# passive_balancing.net
KiCad netlist of a schematic drawn in Altium Designer
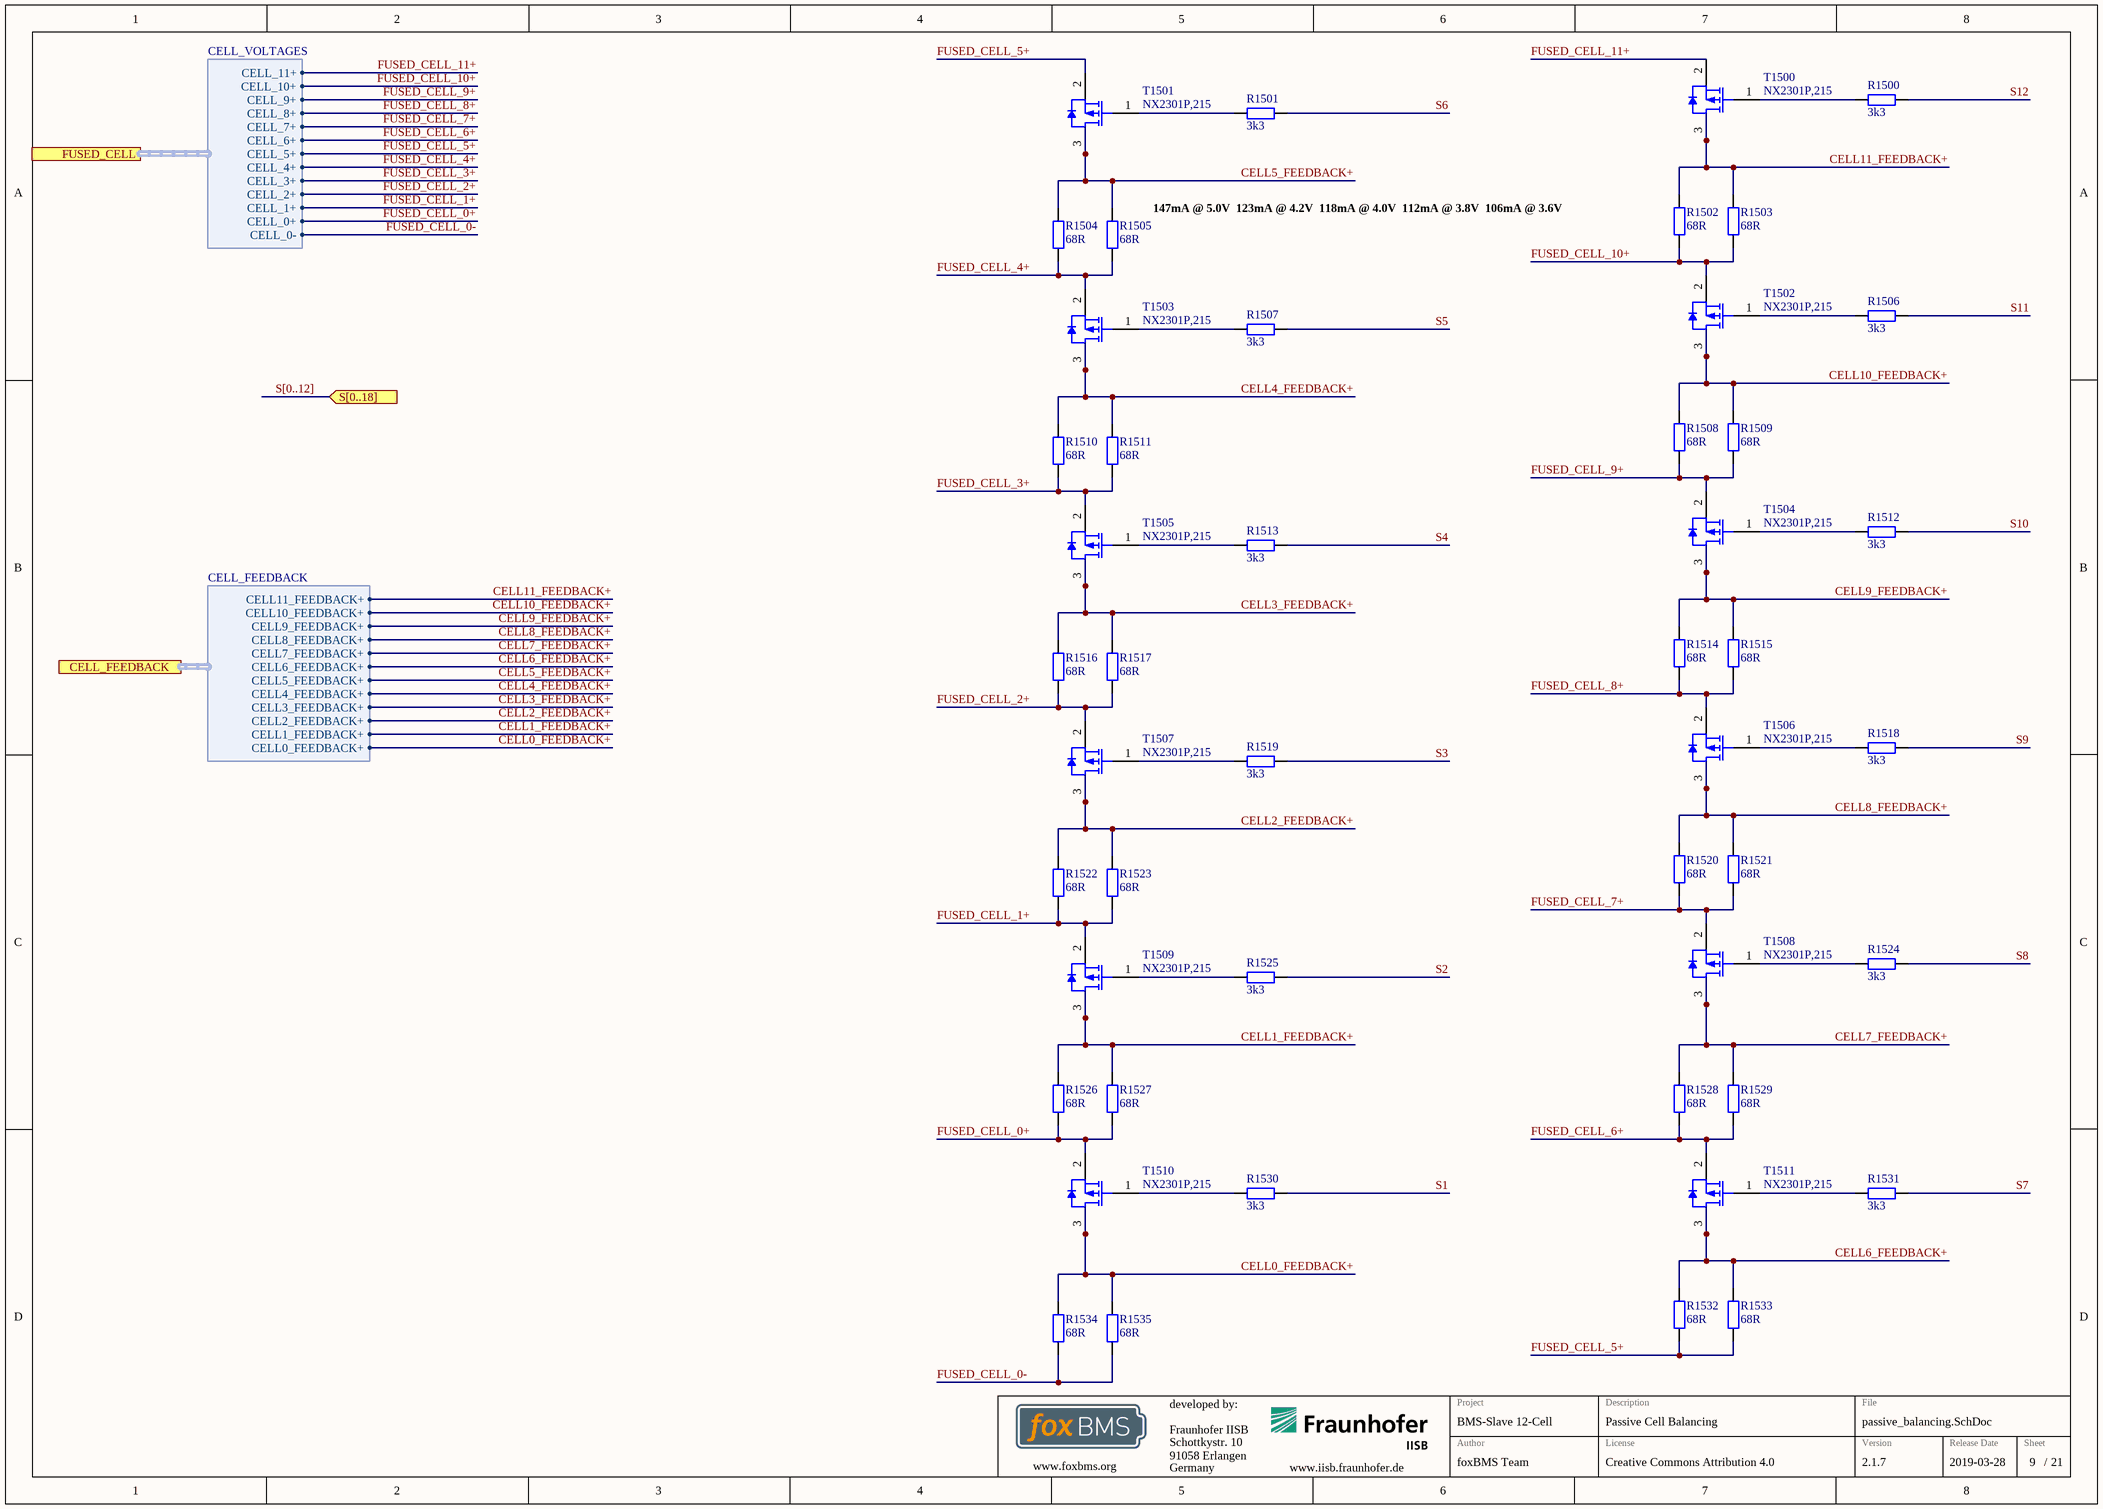
[diagram p0: passive_balancing.SchDoc]

(export (version "E")
  (design (tool "Eeschema 10.0.6"))
  (components
    (comp (ref "R1500")
      (value "3k3")
      (footprint "RESC1608X05N")
      (description "SMD Resistor 3k3 0603")
      (fields (field (name "PART NUMBER") "gen_R_3k3_0603") (field (name "TOLERANCE") "1%"))
      (libsource (lib "OE750") (part "R"))
    )
    (comp (ref "R1501")
      (value "3k3")
      (footprint "RESC1608X05N")
      (description "SMD Resistor 3k3 0603")
      (fields (field (name "PART NUMBER") "gen_R_3k3_0603") (field (name "TOLERANCE") "1%"))
      (libsource (lib "OE750") (part "R"))
    )
    (comp (ref "R1502")
      (value "68R")
      (footprint "RESC5025X07N")
      (description "SMD Resistor 68R 2010")
      (fields (field (name "PART NUMBER") "gen_R_68R_2010") (field (name "TOLERANCE") "1%"))
      (libsource (lib "OE750") (part "R"))
    )
    (comp (ref "R1503")
      (value "68R")
      (footprint "RESC5025X07N")
      (description "SMD Resistor 68R 2010")
      (fields (field (name "PART NUMBER") "gen_R_68R_2010") (field (name "TOLERANCE") "1%"))
      (libsource (lib "OE750") (part "R"))
    )
    (comp (ref "R1504")
      (value "68R")
      (footprint "RESC5025X07N")
      (description "SMD Resistor 68R 2010")
      (fields (field (name "PART NUMBER") "gen_R_68R_2010") (field (name "TOLERANCE") "1%"))
      (libsource (lib "OE750") (part "R"))
    )
    (comp (ref "R1505")
      (value "68R")
      (footprint "RESC5025X07N")
      (description "SMD Resistor 68R 2010")
      (fields (field (name "PART NUMBER") "gen_R_68R_2010") (field (name "TOLERANCE") "1%"))
      (libsource (lib "OE750") (part "R"))
    )
    (comp (ref "R1506")
      (value "3k3")
      (footprint "RESC1608X05N")
      (description "SMD Resistor 3k3 0603")
      (fields (field (name "PART NUMBER") "gen_R_3k3_0603") (field (name "TOLERANCE") "1%"))
      (libsource (lib "OE750") (part "R"))
    )
    (comp (ref "R1507")
      (value "3k3")
      (footprint "RESC1608X05N")
      (description "SMD Resistor 3k3 0603")
      (fields (field (name "PART NUMBER") "gen_R_3k3_0603") (field (name "TOLERANCE") "1%"))
      (libsource (lib "OE750") (part "R"))
    )
    (comp (ref "R1508")
      (value "68R")
      (footprint "RESC5025X07N")
      (description "SMD Resistor 68R 2010")
      (fields (field (name "PART NUMBER") "gen_R_68R_2010") (field (name "TOLERANCE") "1%"))
      (libsource (lib "OE750") (part "R"))
    )
    (comp (ref "R1509")
      (value "68R")
      (footprint "RESC5025X07N")
      (description "SMD Resistor 68R 2010")
      (fields (field (name "PART NUMBER") "gen_R_68R_2010") (field (name "TOLERANCE") "1%"))
      (libsource (lib "OE750") (part "R"))
    )
    (comp (ref "R1510")
      (value "68R")
      (footprint "RESC5025X07N")
      (description "SMD Resistor 68R 2010")
      (fields (field (name "PART NUMBER") "gen_R_68R_2010") (field (name "TOLERANCE") "1%"))
      (libsource (lib "OE750") (part "R"))
    )
    (comp (ref "R1511")
      (value "68R")
      (footprint "RESC5025X07N")
      (description "SMD Resistor 68R 2010")
      (fields (field (name "PART NUMBER") "gen_R_68R_2010") (field (name "TOLERANCE") "1%"))
      (libsource (lib "OE750") (part "R"))
    )
    (comp (ref "R1512")
      (value "3k3")
      (footprint "RESC1608X05N")
      (description "SMD Resistor 3k3 0603")
      (fields (field (name "PART NUMBER") "gen_R_3k3_0603") (field (name "TOLERANCE") "1%"))
      (libsource (lib "OE750") (part "R"))
    )
    (comp (ref "R1513")
      (value "3k3")
      (footprint "RESC1608X05N")
      (description "SMD Resistor 3k3 0603")
      (fields (field (name "PART NUMBER") "gen_R_3k3_0603") (field (name "TOLERANCE") "1%"))
      (libsource (lib "OE750") (part "R"))
    )
    (comp (ref "R1514")
      (value "68R")
      (footprint "RESC5025X07N")
      (description "SMD Resistor 68R 2010")
      (fields (field (name "PART NUMBER") "gen_R_68R_2010") (field (name "TOLERANCE") "1%"))
      (libsource (lib "OE750") (part "R"))
    )
    (comp (ref "R1515")
      (value "68R")
      (footprint "RESC5025X07N")
      (description "SMD Resistor 68R 2010")
      (fields (field (name "PART NUMBER") "gen_R_68R_2010") (field (name "TOLERANCE") "1%"))
      (libsource (lib "OE750") (part "R"))
    )
    (comp (ref "R1516")
      (value "68R")
      (footprint "RESC5025X07N")
      (description "SMD Resistor 68R 2010")
      (fields (field (name "PART NUMBER") "gen_R_68R_2010") (field (name "TOLERANCE") "1%"))
      (libsource (lib "OE750") (part "R"))
    )
    (comp (ref "R1517")
      (value "68R")
      (footprint "RESC5025X07N")
      (description "SMD Resistor 68R 2010")
      (fields (field (name "PART NUMBER") "gen_R_68R_2010") (field (name "TOLERANCE") "1%"))
      (libsource (lib "OE750") (part "R"))
    )
    (comp (ref "R1518")
      (value "3k3")
      (footprint "RESC1608X05N")
      (description "SMD Resistor 3k3 0603")
      (fields (field (name "PART NUMBER") "gen_R_3k3_0603") (field (name "TOLERANCE") "1%"))
      (libsource (lib "OE750") (part "R"))
    )
    (comp (ref "R1519")
      (value "3k3")
      (footprint "RESC1608X05N")
      (description "SMD Resistor 3k3 0603")
      (fields (field (name "PART NUMBER") "gen_R_3k3_0603") (field (name "TOLERANCE") "1%"))
      (libsource (lib "OE750") (part "R"))
    )
    (comp (ref "R1520")
      (value "68R")
      (footprint "RESC5025X07N")
      (description "SMD Resistor 68R 2010")
      (fields (field (name "PART NUMBER") "gen_R_68R_2010") (field (name "TOLERANCE") "1%"))
      (libsource (lib "OE750") (part "R"))
    )
    (comp (ref "R1521")
      (value "68R")
      (footprint "RESC5025X07N")
      (description "SMD Resistor 68R 2010")
      (fields (field (name "PART NUMBER") "gen_R_68R_2010") (field (name "TOLERANCE") "1%"))
      (libsource (lib "OE750") (part "R"))
    )
    (comp (ref "R1522")
      (value "68R")
      (footprint "RESC5025X07N")
      (description "SMD Resistor 68R 2010")
      (fields (field (name "PART NUMBER") "gen_R_68R_2010") (field (name "TOLERANCE") "1%"))
      (libsource (lib "OE750") (part "R"))
    )
    (comp (ref "R1523")
      (value "68R")
      (footprint "RESC5025X07N")
      (description "SMD Resistor 68R 2010")
      (fields (field (name "PART NUMBER") "gen_R_68R_2010") (field (name "TOLERANCE") "1%"))
      (libsource (lib "OE750") (part "R"))
    )
    (comp (ref "R1524")
      (value "3k3")
      (footprint "RESC1608X05N")
      (description "SMD Resistor 3k3 0603")
      (fields (field (name "PART NUMBER") "gen_R_3k3_0603") (field (name "TOLERANCE") "1%"))
      (libsource (lib "OE750") (part "R"))
    )
    (comp (ref "R1525")
      (value "3k3")
      (footprint "RESC1608X05N")
      (description "SMD Resistor 3k3 0603")
      (fields (field (name "PART NUMBER") "gen_R_3k3_0603") (field (name "TOLERANCE") "1%"))
      (libsource (lib "OE750") (part "R"))
    )
    (comp (ref "R1526")
      (value "68R")
      (footprint "RESC5025X07N")
      (description "SMD Resistor 68R 2010")
      (fields (field (name "PART NUMBER") "gen_R_68R_2010") (field (name "TOLERANCE") "1%"))
      (libsource (lib "OE750") (part "R"))
    )
    (comp (ref "R1527")
      (value "68R")
      (footprint "RESC5025X07N")
      (description "SMD Resistor 68R 2010")
      (fields (field (name "PART NUMBER") "gen_R_68R_2010") (field (name "TOLERANCE") "1%"))
      (libsource (lib "OE750") (part "R"))
    )
    (comp (ref "R1528")
      (value "68R")
      (footprint "RESC5025X07N")
      (description "SMD Resistor 68R 2010")
      (fields (field (name "PART NUMBER") "gen_R_68R_2010") (field (name "TOLERANCE") "1%"))
      (libsource (lib "OE750") (part "R"))
    )
    (comp (ref "R1529")
      (value "68R")
      (footprint "RESC5025X07N")
      (description "SMD Resistor 68R 2010")
      (fields (field (name "PART NUMBER") "gen_R_68R_2010") (field (name "TOLERANCE") "1%"))
      (libsource (lib "OE750") (part "R"))
    )
    (comp (ref "R1530")
      (value "3k3")
      (footprint "RESC1608X05N")
      (description "SMD Resistor 3k3 0603")
      (fields (field (name "PART NUMBER") "gen_R_3k3_0603") (field (name "TOLERANCE") "1%"))
      (libsource (lib "OE750") (part "R"))
    )
    (comp (ref "R1531")
      (value "3k3")
      (footprint "RESC1608X05N")
      (description "SMD Resistor 3k3 0603")
      (fields (field (name "PART NUMBER") "gen_R_3k3_0603") (field (name "TOLERANCE") "1%"))
      (libsource (lib "OE750") (part "R"))
    )
    (comp (ref "R1532")
      (value "68R")
      (footprint "RESC5025X07N")
      (description "SMD Resistor 68R 2010")
      (fields (field (name "PART NUMBER") "gen_R_68R_2010") (field (name "TOLERANCE") "1%"))
      (libsource (lib "OE750") (part "R"))
    )
    (comp (ref "R1533")
      (value "68R")
      (footprint "RESC5025X07N")
      (description "SMD Resistor 68R 2010")
      (fields (field (name "PART NUMBER") "gen_R_68R_2010") (field (name "TOLERANCE") "1%"))
      (libsource (lib "OE750") (part "R"))
    )
    (comp (ref "R1534")
      (value "68R")
      (footprint "RESC5025X07N")
      (description "SMD Resistor 68R 2010")
      (fields (field (name "PART NUMBER") "gen_R_68R_2010") (field (name "TOLERANCE") "1%"))
      (libsource (lib "OE750") (part "R"))
    )
    (comp (ref "R1535")
      (value "68R")
      (footprint "RESC5025X07N")
      (description "SMD Resistor 68R 2010")
      (fields (field (name "PART NUMBER") "gen_R_68R_2010") (field (name "TOLERANCE") "1%"))
      (libsource (lib "OE750") (part "R"))
    )
    (comp (ref "T1500")
      (value "NX2301P,215")
      (footprint "NXP-SOT23_N")
      (description "P-Channel Trench MOSFET, -20 V, -2 A, -55 to 150 degC, 3-Pin SOT23, Tape and Reel")
      (fields (field (name "MANUFACTURER") "NXP Semiconductors"))
      (libsource (lib "Altium Content Vault") (part "NXP-PMOS-GSD-3"))
    )
    (comp (ref "T1501")
      (value "NX2301P,215")
      (footprint "NXP-SOT23_N")
      (description "P-Channel Trench MOSFET, -20 V, -2 A, -55 to 150 degC, 3-Pin SOT23, Tape and Reel")
      (fields (field (name "MANUFACTURER") "NXP Semiconductors"))
      (libsource (lib "Altium Content Vault") (part "NXP-PMOS-GSD-3"))
    )
    (comp (ref "T1502")
      (value "NX2301P,215")
      (footprint "NXP-SOT23_N")
      (description "P-Channel Trench MOSFET, -20 V, -2 A, -55 to 150 degC, 3-Pin SOT23, Tape and Reel")
      (fields (field (name "MANUFACTURER") "NXP Semiconductors"))
      (libsource (lib "Altium Content Vault") (part "NXP-PMOS-GSD-3"))
    )
    (comp (ref "T1503")
      (value "NX2301P,215")
      (footprint "NXP-SOT23_N")
      (description "P-Channel Trench MOSFET, -20 V, -2 A, -55 to 150 degC, 3-Pin SOT23, Tape and Reel")
      (fields (field (name "MANUFACTURER") "NXP Semiconductors"))
      (libsource (lib "Altium Content Vault") (part "NXP-PMOS-GSD-3"))
    )
    (comp (ref "T1504")
      (value "NX2301P,215")
      (footprint "NXP-SOT23_N")
      (description "P-Channel Trench MOSFET, -20 V, -2 A, -55 to 150 degC, 3-Pin SOT23, Tape and Reel")
      (fields (field (name "MANUFACTURER") "NXP Semiconductors"))
      (libsource (lib "Altium Content Vault") (part "NXP-PMOS-GSD-3"))
    )
    (comp (ref "T1505")
      (value "NX2301P,215")
      (footprint "NXP-SOT23_N")
      (description "P-Channel Trench MOSFET, -20 V, -2 A, -55 to 150 degC, 3-Pin SOT23, Tape and Reel")
      (fields (field (name "MANUFACTURER") "NXP Semiconductors"))
      (libsource (lib "Altium Content Vault") (part "NXP-PMOS-GSD-3"))
    )
    (comp (ref "T1506")
      (value "NX2301P,215")
      (footprint "NXP-SOT23_N")
      (description "P-Channel Trench MOSFET, -20 V, -2 A, -55 to 150 degC, 3-Pin SOT23, Tape and Reel")
      (fields (field (name "MANUFACTURER") "NXP Semiconductors"))
      (libsource (lib "Altium Content Vault") (part "NXP-PMOS-GSD-3"))
    )
    (comp (ref "T1507")
      (value "NX2301P,215")
      (footprint "NXP-SOT23_N")
      (description "P-Channel Trench MOSFET, -20 V, -2 A, -55 to 150 degC, 3-Pin SOT23, Tape and Reel")
      (fields (field (name "MANUFACTURER") "NXP Semiconductors"))
      (libsource (lib "Altium Content Vault") (part "NXP-PMOS-GSD-3"))
    )
    (comp (ref "T1508")
      (value "NX2301P,215")
      (footprint "NXP-SOT23_N")
      (description "P-Channel Trench MOSFET, -20 V, -2 A, -55 to 150 degC, 3-Pin SOT23, Tape and Reel")
      (fields (field (name "MANUFACTURER") "NXP Semiconductors"))
      (libsource (lib "Altium Content Vault") (part "NXP-PMOS-GSD-3"))
    )
    (comp (ref "T1509")
      (value "NX2301P,215")
      (footprint "NXP-SOT23_N")
      (description "P-Channel Trench MOSFET, -20 V, -2 A, -55 to 150 degC, 3-Pin SOT23, Tape and Reel")
      (fields (field (name "MANUFACTURER") "NXP Semiconductors"))
      (libsource (lib "Altium Content Vault") (part "NXP-PMOS-GSD-3"))
    )
    (comp (ref "T1510")
      (value "NX2301P,215")
      (footprint "NXP-SOT23_N")
      (description "P-Channel Trench MOSFET, -20 V, -2 A, -55 to 150 degC, 3-Pin SOT23, Tape and Reel")
      (fields (field (name "MANUFACTURER") "NXP Semiconductors"))
      (libsource (lib "Altium Content Vault") (part "NXP-PMOS-GSD-3"))
    )
    (comp (ref "T1511")
      (value "NX2301P,215")
      (footprint "NXP-SOT23_N")
      (description "P-Channel Trench MOSFET, -20 V, -2 A, -55 to 150 degC, 3-Pin SOT23, Tape and Reel")
      (fields (field (name "MANUFACTURER") "NXP Semiconductors"))
      (libsource (lib "Altium Content Vault") (part "NXP-PMOS-GSD-3"))
    )
  )
  (nets
    (net (code "4") (name "/CELL0_FEEDBACK+") (class "Default")
      (node (ref "R1534") (pin "2") (pinfunction "2_2") (pintype "passive"))
      (node (ref "R1535") (pin "2") (pinfunction "2_2") (pintype "passive"))
      (node (ref "T1510") (pin "3") (pinfunction "D_3") (pintype "passive"))
    )
    (net (code "5") (name "/CELL1_FEEDBACK+") (class "Default")
      (node (ref "R1526") (pin "2") (pinfunction "2_2") (pintype "passive"))
      (node (ref "R1527") (pin "2") (pinfunction "2_2") (pintype "passive"))
      (node (ref "T1509") (pin "3") (pinfunction "D_3") (pintype "passive"))
    )
    (net (code "6") (name "/CELL2_FEEDBACK+") (class "Default")
      (node (ref "R1522") (pin "2") (pinfunction "2_2") (pintype "passive"))
      (node (ref "R1523") (pin "2") (pinfunction "2_2") (pintype "passive"))
      (node (ref "T1507") (pin "3") (pinfunction "D_3") (pintype "passive"))
    )
    (net (code "7") (name "/CELL3_FEEDBACK+") (class "Default")
      (node (ref "R1516") (pin "2") (pinfunction "2_2") (pintype "passive"))
      (node (ref "R1517") (pin "2") (pinfunction "2_2") (pintype "passive"))
      (node (ref "T1505") (pin "3") (pinfunction "D_3") (pintype "passive"))
    )
    (net (code "8") (name "/CELL4_FEEDBACK+") (class "Default")
      (node (ref "R1510") (pin "2") (pinfunction "2_2") (pintype "passive"))
      (node (ref "R1511") (pin "2") (pinfunction "2_2") (pintype "passive"))
      (node (ref "T1503") (pin "3") (pinfunction "D_3") (pintype "passive"))
    )
    (net (code "9") (name "/CELL5_FEEDBACK+") (class "Default")
      (node (ref "R1504") (pin "2") (pinfunction "2_2") (pintype "passive"))
      (node (ref "R1505") (pin "2") (pinfunction "2_2") (pintype "passive"))
      (node (ref "T1501") (pin "3") (pinfunction "D_3") (pintype "passive"))
    )
    (net (code "10") (name "/CELL6_FEEDBACK+") (class "Default")
      (node (ref "R1532") (pin "2") (pinfunction "2_2") (pintype "passive"))
      (node (ref "R1533") (pin "2") (pinfunction "2_2") (pintype "passive"))
      (node (ref "T1511") (pin "3") (pinfunction "D_3") (pintype "passive"))
    )
    (net (code "11") (name "/CELL7_FEEDBACK+") (class "Default")
      (node (ref "R1528") (pin "2") (pinfunction "2_2") (pintype "passive"))
      (node (ref "R1529") (pin "2") (pinfunction "2_2") (pintype "passive"))
      (node (ref "T1508") (pin "3") (pinfunction "D_3") (pintype "passive"))
    )
    (net (code "12") (name "/CELL8_FEEDBACK+") (class "Default")
      (node (ref "R1520") (pin "2") (pinfunction "2_2") (pintype "passive"))
      (node (ref "R1521") (pin "2") (pinfunction "2_2") (pintype "passive"))
      (node (ref "T1506") (pin "3") (pinfunction "D_3") (pintype "passive"))
    )
    (net (code "13") (name "/CELL9_FEEDBACK+") (class "Default")
      (node (ref "R1514") (pin "2") (pinfunction "2_2") (pintype "passive"))
      (node (ref "R1515") (pin "2") (pinfunction "2_2") (pintype "passive"))
      (node (ref "T1504") (pin "3") (pinfunction "D_3") (pintype "passive"))
    )
    (net (code "14") (name "/CELL10_FEEDBACK+") (class "Default")
      (node (ref "R1508") (pin "2") (pinfunction "2_2") (pintype "passive"))
      (node (ref "R1509") (pin "2") (pinfunction "2_2") (pintype "passive"))
      (node (ref "T1502") (pin "3") (pinfunction "D_3") (pintype "passive"))
    )
    (net (code "15") (name "/CELL11_FEEDBACK+") (class "Default")
      (node (ref "R1502") (pin "2") (pinfunction "2_2") (pintype "passive"))
      (node (ref "R1503") (pin "2") (pinfunction "2_2") (pintype "passive"))
      (node (ref "T1500") (pin "3") (pinfunction "D_3") (pintype "passive"))
    )
    (net (code "16") (name "/FUSED_CELL_0+") (class "Default")
      (node (ref "R1526") (pin "1") (pinfunction "1_1") (pintype "passive"))
      (node (ref "R1527") (pin "1") (pinfunction "1_1") (pintype "passive"))
      (node (ref "T1510") (pin "2") (pinfunction "S_2") (pintype "passive"))
    )
    (net (code "17") (name "/FUSED_CELL_0-") (class "Default")
      (node (ref "R1534") (pin "1") (pinfunction "1_1") (pintype "passive"))
      (node (ref "R1535") (pin "1") (pinfunction "1_1") (pintype "passive"))
    )
    (net (code "18") (name "/FUSED_CELL_1+") (class "Default")
      (node (ref "R1522") (pin "1") (pinfunction "1_1") (pintype "passive"))
      (node (ref "R1523") (pin "1") (pinfunction "1_1") (pintype "passive"))
      (node (ref "T1509") (pin "2") (pinfunction "S_2") (pintype "passive"))
    )
    (net (code "19") (name "/FUSED_CELL_2+") (class "Default")
      (node (ref "R1516") (pin "1") (pinfunction "1_1") (pintype "passive"))
      (node (ref "R1517") (pin "1") (pinfunction "1_1") (pintype "passive"))
      (node (ref "T1507") (pin "2") (pinfunction "S_2") (pintype "passive"))
    )
    (net (code "20") (name "/FUSED_CELL_3+") (class "Default")
      (node (ref "R1510") (pin "1") (pinfunction "1_1") (pintype "passive"))
      (node (ref "R1511") (pin "1") (pinfunction "1_1") (pintype "passive"))
      (node (ref "T1505") (pin "2") (pinfunction "S_2") (pintype "passive"))
    )
    (net (code "21") (name "/FUSED_CELL_4+") (class "Default")
      (node (ref "R1504") (pin "1") (pinfunction "1_1") (pintype "passive"))
      (node (ref "R1505") (pin "1") (pinfunction "1_1") (pintype "passive"))
      (node (ref "T1503") (pin "2") (pinfunction "S_2") (pintype "passive"))
    )
    (net (code "22") (name "/FUSED_CELL_5+") (class "Default")
      (node (ref "R1532") (pin "1") (pinfunction "1_1") (pintype "passive"))
      (node (ref "R1533") (pin "1") (pinfunction "1_1") (pintype "passive"))
      (node (ref "T1501") (pin "2") (pinfunction "S_2") (pintype "passive"))
    )
    (net (code "23") (name "/FUSED_CELL_6+") (class "Default")
      (node (ref "R1528") (pin "1") (pinfunction "1_1") (pintype "passive"))
      (node (ref "R1529") (pin "1") (pinfunction "1_1") (pintype "passive"))
      (node (ref "T1511") (pin "2") (pinfunction "S_2") (pintype "passive"))
    )
    (net (code "24") (name "/FUSED_CELL_7+") (class "Default")
      (node (ref "R1520") (pin "1") (pinfunction "1_1") (pintype "passive"))
      (node (ref "R1521") (pin "1") (pinfunction "1_1") (pintype "passive"))
      (node (ref "T1508") (pin "2") (pinfunction "S_2") (pintype "passive"))
    )
    (net (code "25") (name "/FUSED_CELL_8+") (class "Default")
      (node (ref "R1514") (pin "1") (pinfunction "1_1") (pintype "passive"))
      (node (ref "R1515") (pin "1") (pinfunction "1_1") (pintype "passive"))
      (node (ref "T1506") (pin "2") (pinfunction "S_2") (pintype "passive"))
    )
    (net (code "26") (name "/FUSED_CELL_9+") (class "Default")
      (node (ref "R1508") (pin "1") (pinfunction "1_1") (pintype "passive"))
      (node (ref "R1509") (pin "1") (pinfunction "1_1") (pintype "passive"))
      (node (ref "T1504") (pin "2") (pinfunction "S_2") (pintype "passive"))
    )
    (net (code "27") (name "/FUSED_CELL_10+") (class "Default")
      (node (ref "R1502") (pin "1") (pinfunction "1_1") (pintype "passive"))
      (node (ref "R1503") (pin "1") (pinfunction "1_1") (pintype "passive"))
      (node (ref "T1502") (pin "2") (pinfunction "S_2") (pintype "passive"))
    )
    (net (code "28") (name "/FUSED_CELL_11+") (class "Default")
      (node (ref "T1500") (pin "2") (pinfunction "S_2") (pintype "passive"))
    )
    (net (code "29") (name "/S1") (class "Default")
      (node (ref "R1530") (pin "2") (pinfunction "2_2") (pintype "passive"))
    )
    (net (code "30") (name "/S2") (class "Default")
      (node (ref "R1525") (pin "2") (pinfunction "2_2") (pintype "passive"))
    )
    (net (code "31") (name "/S3") (class "Default")
      (node (ref "R1519") (pin "2") (pinfunction "2_2") (pintype "passive"))
    )
    (net (code "32") (name "/S4") (class "Default")
      (node (ref "R1513") (pin "2") (pinfunction "2_2") (pintype "passive"))
    )
    (net (code "33") (name "/S5") (class "Default")
      (node (ref "R1507") (pin "2") (pinfunction "2_2") (pintype "passive"))
    )
    (net (code "34") (name "/S6") (class "Default")
      (node (ref "R1501") (pin "2") (pinfunction "2_2") (pintype "passive"))
    )
    (net (code "35") (name "/S7") (class "Default")
      (node (ref "R1531") (pin "2") (pinfunction "2_2") (pintype "passive"))
    )
    (net (code "36") (name "/S8") (class "Default")
      (node (ref "R1524") (pin "2") (pinfunction "2_2") (pintype "passive"))
    )
    (net (code "37") (name "/S9") (class "Default")
      (node (ref "R1518") (pin "2") (pinfunction "2_2") (pintype "passive"))
    )
    (net (code "38") (name "/S10") (class "Default")
      (node (ref "R1512") (pin "2") (pinfunction "2_2") (pintype "passive"))
    )
    (net (code "39") (name "/S11") (class "Default")
      (node (ref "R1506") (pin "2") (pinfunction "2_2") (pintype "passive"))
    )
    (net (code "40") (name "/S12") (class "Default")
      (node (ref "R1500") (pin "2") (pinfunction "2_2") (pintype "passive"))
    )
    (net (code "44") (name "Net-(T1500-G)") (class "Default")
      (node (ref "R1500") (pin "1") (pinfunction "1_1") (pintype "passive"))
      (node (ref "T1500") (pin "1") (pinfunction "G_1") (pintype "passive"))
    )
    (net (code "45") (name "Net-(T1501-G)") (class "Default")
      (node (ref "R1501") (pin "1") (pinfunction "1_1") (pintype "passive"))
      (node (ref "T1501") (pin "1") (pinfunction "G_1") (pintype "passive"))
    )
    (net (code "46") (name "Net-(T1502-G)") (class "Default")
      (node (ref "R1506") (pin "1") (pinfunction "1_1") (pintype "passive"))
      (node (ref "T1502") (pin "1") (pinfunction "G_1") (pintype "passive"))
    )
    (net (code "47") (name "Net-(T1503-G)") (class "Default")
      (node (ref "R1507") (pin "1") (pinfunction "1_1") (pintype "passive"))
      (node (ref "T1503") (pin "1") (pinfunction "G_1") (pintype "passive"))
    )
    (net (code "48") (name "Net-(T1504-G)") (class "Default")
      (node (ref "R1512") (pin "1") (pinfunction "1_1") (pintype "passive"))
      (node (ref "T1504") (pin "1") (pinfunction "G_1") (pintype "passive"))
    )
    (net (code "49") (name "Net-(T1505-G)") (class "Default")
      (node (ref "R1513") (pin "1") (pinfunction "1_1") (pintype "passive"))
      (node (ref "T1505") (pin "1") (pinfunction "G_1") (pintype "passive"))
    )
    (net (code "50") (name "Net-(T1506-G)") (class "Default")
      (node (ref "R1518") (pin "1") (pinfunction "1_1") (pintype "passive"))
      (node (ref "T1506") (pin "1") (pinfunction "G_1") (pintype "passive"))
    )
    (net (code "51") (name "Net-(T1507-G)") (class "Default")
      (node (ref "R1519") (pin "1") (pinfunction "1_1") (pintype "passive"))
      (node (ref "T1507") (pin "1") (pinfunction "G_1") (pintype "passive"))
    )
    (net (code "52") (name "Net-(T1508-G)") (class "Default")
      (node (ref "R1524") (pin "1") (pinfunction "1_1") (pintype "passive"))
      (node (ref "T1508") (pin "1") (pinfunction "G_1") (pintype "passive"))
    )
    (net (code "53") (name "Net-(T1509-G)") (class "Default")
      (node (ref "R1525") (pin "1") (pinfunction "1_1") (pintype "passive"))
      (node (ref "T1509") (pin "1") (pinfunction "G_1") (pintype "passive"))
    )
    (net (code "54") (name "Net-(T1510-G)") (class "Default")
      (node (ref "R1530") (pin "1") (pinfunction "1_1") (pintype "passive"))
      (node (ref "T1510") (pin "1") (pinfunction "G_1") (pintype "passive"))
    )
    (net (code "55") (name "Net-(T1511-G)") (class "Default")
      (node (ref "R1531") (pin "1") (pinfunction "1_1") (pintype "passive"))
      (node (ref "T1511") (pin "1") (pinfunction "G_1") (pintype "passive"))
    )
  )
)
